# power.net
KiCad netlist of a schematic drawn in Altium Designer
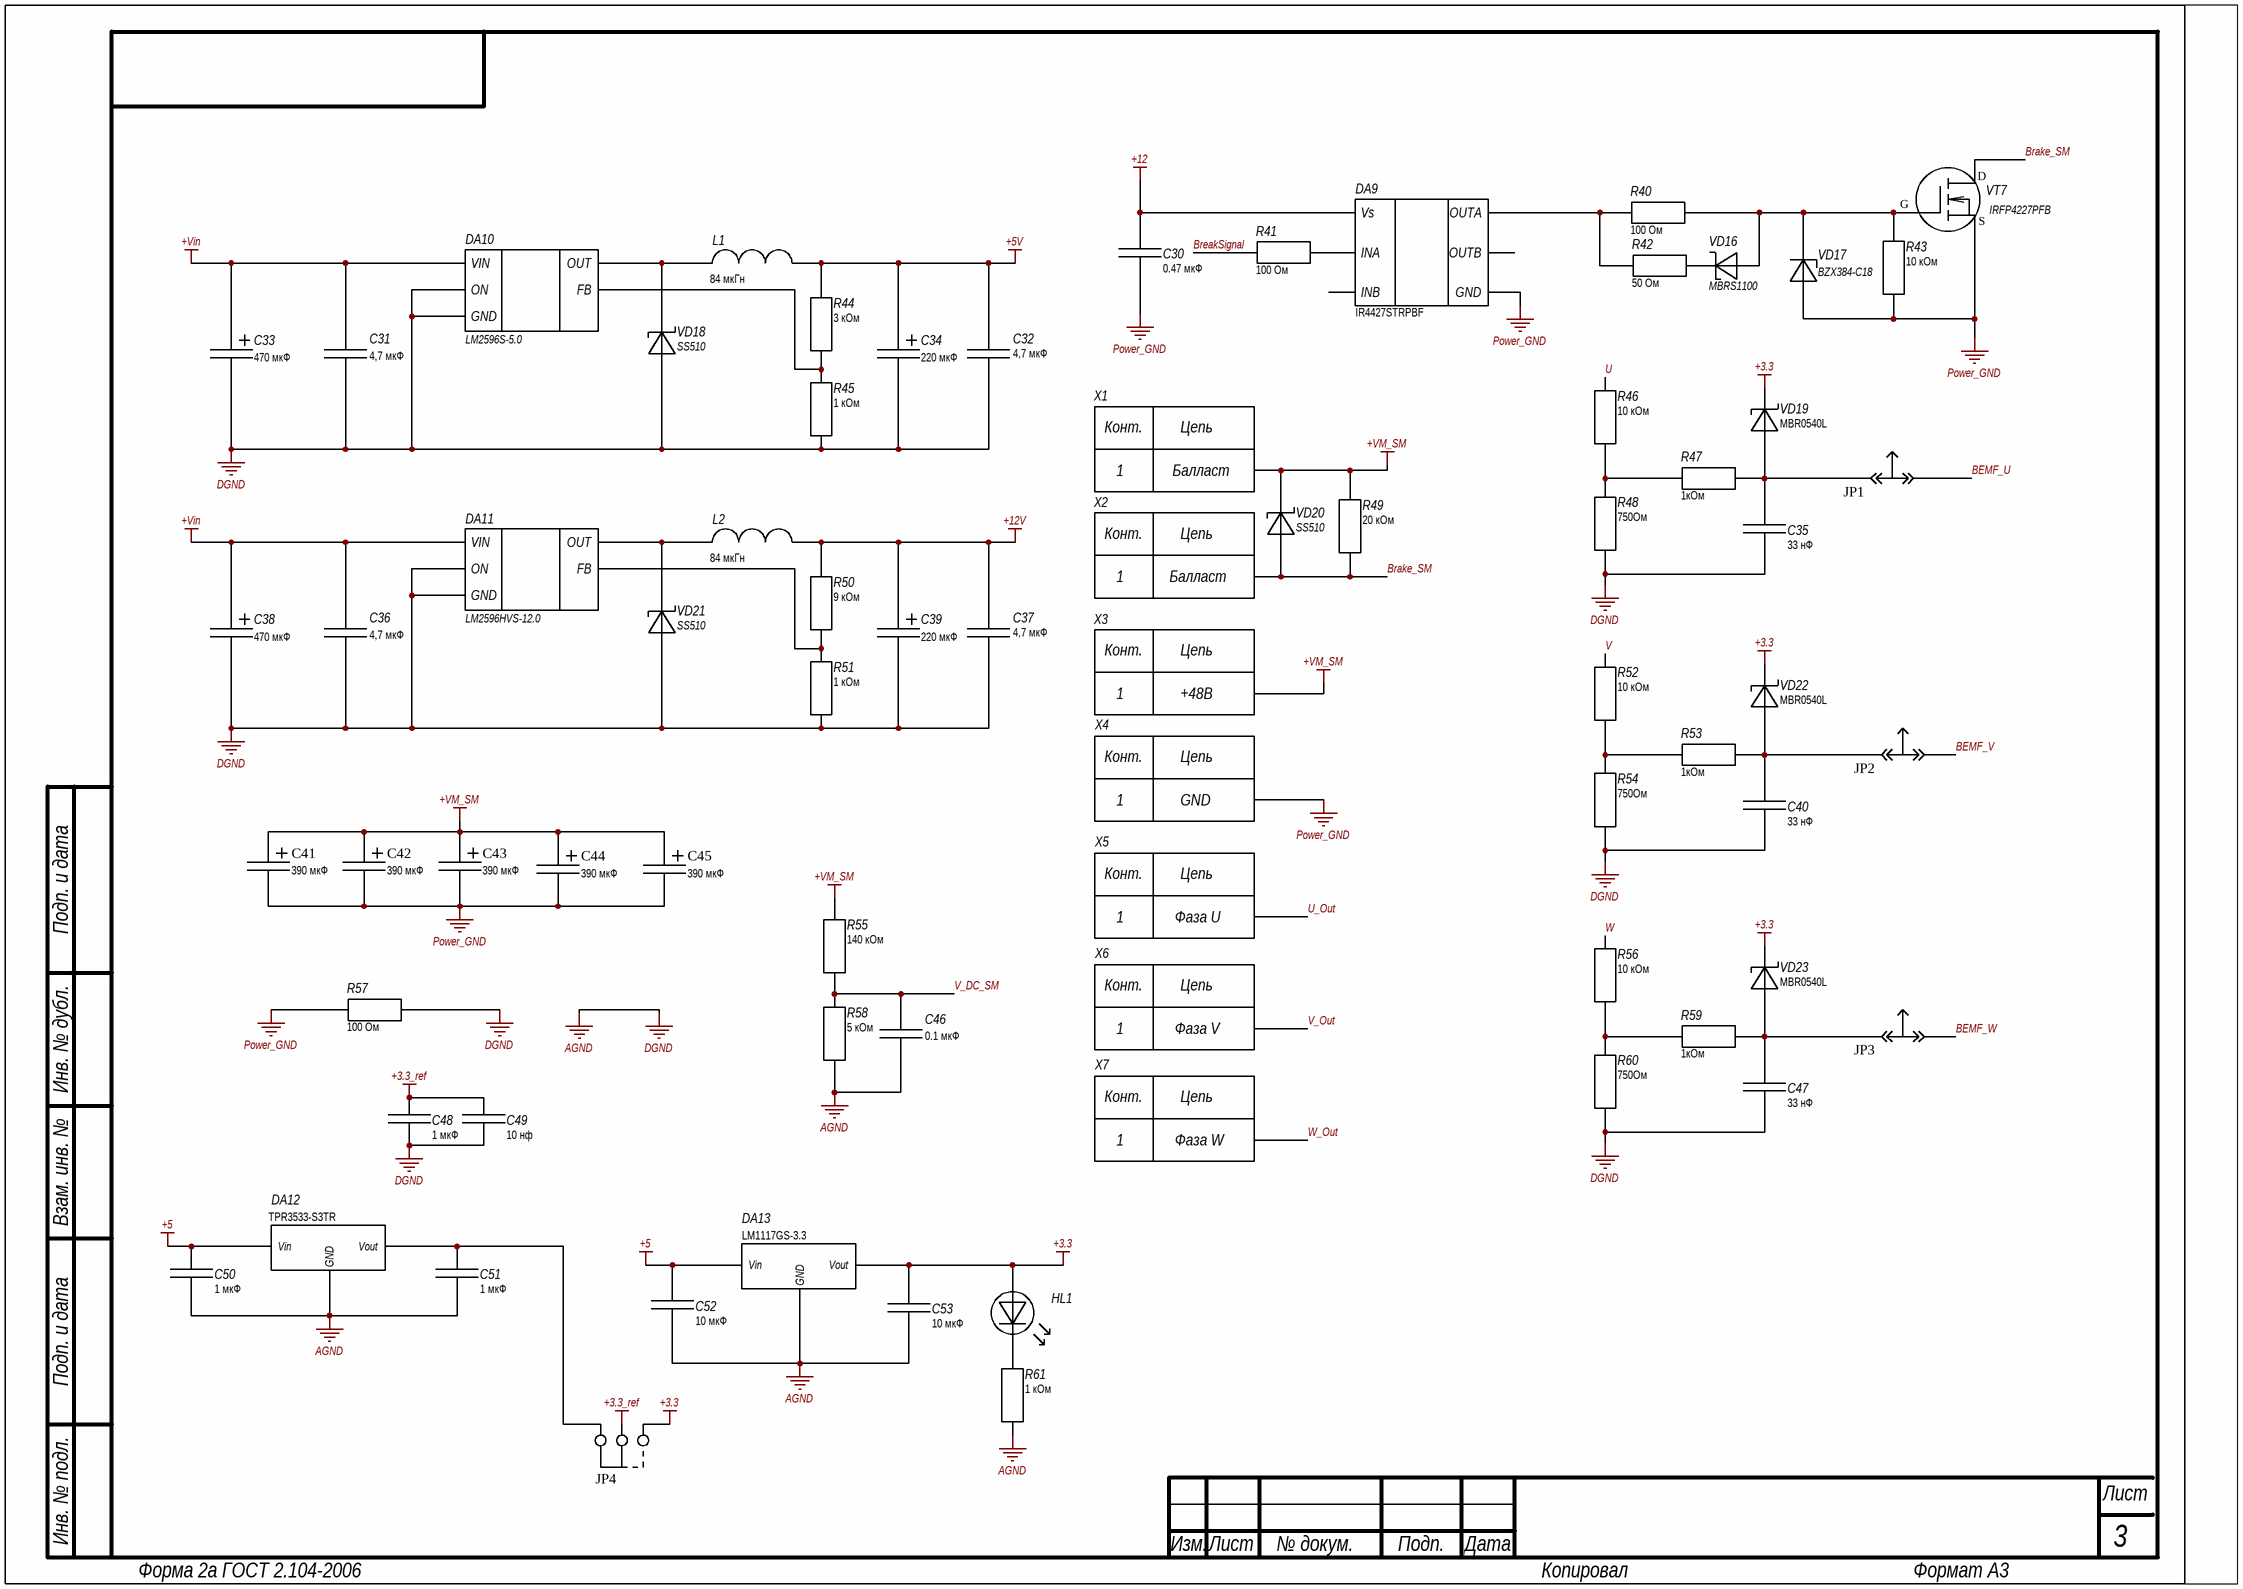
[diagram p0: power.SchDoc]

(export (version "E")
  (design (tool "Eeschema 10.0.6"))
  (components
    (comp (ref "1")
      (value "Net Tie")
      (footprint "Net Tie")
      (libsource (lib "Main_components") (part "Net Tie"))
    )
    (comp (ref "C30")
      (value "0.47 мкФ")
      (footprint "CC1206")
      (fields (field (name "VOLTAGE") "50В") (field (name "Comment") "Capacitor"))
      (libsource (lib "Main_components") (part "Capacitor"))
    )
    (comp (ref "C31")
      (value "4,7 мкФ")
      (footprint "CC1206")
      (fields (field (name "VOLTAGE") "50 В") (field (name "Comment") "Capacitor"))
      (libsource (lib "Main_components") (part "Capacitor"))
    )
    (comp (ref "C32")
      (value "4,7 мкФ")
      (footprint "CC1206")
      (fields (field (name "VOLTAGE") "50 В") (field (name "Comment") "Capacitor"))
      (libsource (lib "Main_components") (part "Capacitor"))
    )
    (comp (ref "C33")
      (value "470 мкФ")
      (footprint "CAP-5-12.5")
      (fields (field (name "VOLTAGE") " 50 В") (field (name "Comment") "EXR471M50B"))
      (libsource (lib "Main_components") (part "Сapacitor pol"))
    )
    (comp (ref "C34")
      (value "220 мкФ")
      (footprint "CAP-5-10")
      (fields (field (name "VOLTAGE") "35 В") (field (name "Comment") "B41858C7227M"))
      (libsource (lib "Main_components") (part "Сapacitor pol"))
    )
    (comp (ref "C35")
      (value "33 нФ")
      (footprint "CC0805")
      (fields (field (name "VOLTAGE") "50В") (field (name "Comment") "Capacitor"))
      (libsource (lib "Main_components") (part "Capacitor"))
    )
    (comp (ref "C36")
      (value "4,7 мкФ")
      (footprint "CC1206")
      (fields (field (name "VOLTAGE") "50 В") (field (name "Comment") "Capacitor"))
      (libsource (lib "Main_components") (part "Capacitor"))
    )
    (comp (ref "C37")
      (value "4,7 мкФ")
      (footprint "CC1206")
      (fields (field (name "VOLTAGE") "50 В") (field (name "Comment") "Capacitor"))
      (libsource (lib "Main_components") (part "Capacitor"))
    )
    (comp (ref "C38")
      (value "470 мкФ")
      (footprint "CAP-5-12.5")
      (fields (field (name "VOLTAGE") " 50 В") (field (name "Comment") "EXR471M50B"))
      (libsource (lib "Main_components") (part "Сapacitor pol"))
    )
    (comp (ref "C39")
      (value "220 мкФ")
      (footprint "CAP-5-10")
      (fields (field (name "VOLTAGE") "35 В") (field (name "Comment") "B41858C7227M"))
      (libsource (lib "Main_components") (part "Сapacitor pol"))
    )
    (comp (ref "C40")
      (value "33 нФ")
      (footprint "CC0805")
      (fields (field (name "VOLTAGE") "50В") (field (name "Comment") "Capacitor"))
      (libsource (lib "Main_components") (part "Capacitor"))
    )
    (comp (ref "C41")
      (value "390 мкФ")
      (footprint "CAP-7.5-18")
      (fields (field (name "Comment") "Сapacitor pol"))
      (libsource (lib "Main_components") (part "Сapacitor pol"))
    )
    (comp (ref "C42")
      (value "390 мкФ")
      (footprint "CAP-7.5-18")
      (fields (field (name "Comment") "Сapacitor pol"))
      (libsource (lib "Main_components") (part "Сapacitor pol"))
    )
    (comp (ref "C43")
      (value "390 мкФ")
      (footprint "CAP-7.5-18")
      (fields (field (name "Comment") "Сapacitor pol"))
      (libsource (lib "Main_components") (part "Сapacitor pol"))
    )
    (comp (ref "C44")
      (value "390 мкФ")
      (footprint "CAP-7.5-18")
      (fields (field (name "Comment") "Сapacitor pol"))
      (libsource (lib "Main_components") (part "Сapacitor pol"))
    )
    (comp (ref "C45")
      (value "390 мкФ")
      (footprint "CAP-7.5-18")
      (fields (field (name "Comment") "Сapacitor pol"))
      (libsource (lib "Main_components") (part "Сapacitor pol"))
    )
    (comp (ref "C46")
      (value "0.1 мкФ")
      (footprint "CC0603")
      (fields (field (name "VOLTAGE") "50 В") (field (name "Comment") "Capacitor"))
      (libsource (lib "Main_components") (part "Capacitor"))
    )
    (comp (ref "C47")
      (value "33 нФ")
      (footprint "CC0805")
      (fields (field (name "VOLTAGE") "50В") (field (name "Comment") "Capacitor"))
      (libsource (lib "Main_components") (part "Capacitor"))
    )
    (comp (ref "C48")
      (value "1 мкФ")
      (footprint "CC0603")
      (fields (field (name "VOLTAGE") "10В") (field (name "Comment") "Capacitor"))
      (libsource (lib "Main_components") (part "Capacitor"))
    )
    (comp (ref "C49")
      (value "10 нф")
      (footprint "CC0402")
      (fields (field (name "VOLTAGE") "16В") (field (name "Comment") "Capacitor"))
      (libsource (lib "Main_components") (part "Capacitor"))
    )
    (comp (ref "C50")
      (value "1 мкФ")
      (footprint "CC0805")
      (fields (field (name "VOLTAGE") " 25 В") (field (name "Comment") "Capacitor"))
      (libsource (lib "Main_components") (part "Capacitor"))
    )
    (comp (ref "C51")
      (value "1 мкФ")
      (footprint "CC0805")
      (fields (field (name "VOLTAGE") " 25 В") (field (name "Comment") "Capacitor"))
      (libsource (lib "Main_components") (part "Capacitor"))
    )
    (comp (ref "C52")
      (value "10 мкФ")
      (footprint "CC1206")
      (fields (field (name "VOLTAGE") " 25 В") (field (name "Comment") "Capacitor"))
      (libsource (lib "Main_components") (part "Capacitor"))
    )
    (comp (ref "C53")
      (value "10 мкФ")
      (footprint "CC1206")
      (fields (field (name "VOLTAGE") " 25 В") (field (name "Comment") "Capacitor"))
      (libsource (lib "Main_components") (part "Capacitor"))
    )
    (comp (ref "DA9")
      (value "IR4427STRPBF")
      (footprint "SO8")
      (description "Драйвер сдвоенный нижнего плеча 8SOIC")
      (libsource (lib "Microcircuits") (part "IR4427STRPBF"))
    )
    (comp (ref "DA10")
      (value "LM2596S-5.0")
      (footprint "TO263-5L")
      (libsource (lib "Microcircuits") (part "LM2596"))
    )
    (comp (ref "DA11")
      (value "LM2596HVS-12.0")
      (footprint "TO263-5L")
      (libsource (lib "Microcircuits") (part "LM2596"))
    )
    (comp (ref "DA12")
      (value "TPR3533-S3TR")
      (footprint "SOT-23-5")
      (description "Источник опорного напряжения 3.3В")
      (libsource (lib "Microcircuits") (part "TPR3533-S3TR"))
    )
    (comp (ref "DA13")
      (value "LM1117GS-3.3")
      (footprint "SOT-223")
      (description "Линейный регулятор с низким падением напряжения, +3.3 В, 1А")
      (libsource (lib "Microcircuits") (part "LM1117GS-3.3"))
    )
    (comp (ref "HL1") (value "LED") (footprint "CC1206") (libsource (lib "Main_components") (part "LED")))
    (comp (ref "JP1") (value "Jumper-2") (footprint "PLS2") (libsource (lib "Connectors") (part "Jumper-2")))
    (comp (ref "JP2") (value "Jumper-2") (footprint "PLS2") (libsource (lib "Connectors") (part "Jumper-2")))
    (comp (ref "JP3") (value "Jumper-2") (footprint "PLS2") (libsource (lib "Connectors") (part "Jumper-2")))
    (comp (ref "JP4") (value "Jumper") (footprint "PLS3") (libsource (lib "Connectors") (part "Jumper")))
    (comp (ref "L1")
      (value "84 мкГн")
      (footprint "CDRH127/LDNP-820MC")
      (fields (field (name "Comment") "CDRH127/LDNP-820MC"))
      (libsource (lib "Main_components") (part "Inductor"))
    )
    (comp (ref "L2")
      (value "84 мкГн")
      (footprint "CDRH127/LDNP-820MC")
      (fields (field (name "Comment") "CDRH127/LDNP-820MC"))
      (libsource (lib "Main_components") (part "Inductor"))
    )
    (comp (ref "R40")
      (value "100 Ом")
      (footprint "RC2512")
      (fields (field (name "POWER") "1 Вт") (field (name "Comment") "Resistor"))
      (libsource (lib "Main_components") (part "Resistor"))
    )
    (comp (ref "R41")
      (value "100 Ом")
      (footprint "RC0603")
      (fields (field (name "POWER") "100 мВт") (field (name "Comment") "Resistor"))
      (libsource (lib "Main_components") (part "Resistor"))
    )
    (comp (ref "R42")
      (value "50 Ом")
      (footprint "RC2512")
      (fields (field (name "POWER") "1 Вт") (field (name "Comment") "Resistor"))
      (libsource (lib "") (part "Resistor_1"))
    )
    (comp (ref "R43")
      (value "10 кОм")
      (footprint "RC0805")
      (fields (field (name "POWER") "125 мВт") (field (name "Comment") "Resistor"))
      (libsource (lib "Main_components") (part "Resistor"))
    )
    (comp (ref "R44")
      (value "3 кОм")
      (footprint "RC0805")
      (fields (field (name "POWER") "125 мВт") (field (name "Comment") "Resistor"))
      (libsource (lib "Main_components") (part "Resistor"))
    )
    (comp (ref "R45")
      (value "1 кОм")
      (footprint "RC0805")
      (fields (field (name "POWER") "125 мВт") (field (name "Comment") "Resistor"))
      (libsource (lib "Main_components") (part "Resistor"))
    )
    (comp (ref "R46")
      (value "10 кОм")
      (footprint "RC1206")
      (fields (field (name "POWER") "125 мВт") (field (name "Comment") "Resistor"))
      (libsource (lib "Main_components") (part "Resistor"))
    )
    (comp (ref "R47")
      (value "1кОм")
      (footprint "RC0805")
      (fields (field (name "POWER") "125 мВт") (field (name "Comment") "Resistor"))
      (libsource (lib "Main_components") (part "Resistor"))
    )
    (comp (ref "R48")
      (value "750Ом")
      (footprint "RC1206")
      (fields (field (name "POWER") "125 мВт") (field (name "Comment") "Resistor"))
      (libsource (lib "Main_components") (part "Resistor"))
    )
    (comp (ref "R49")
      (value "20 кОм")
      (footprint "RC1206")
      (fields (field (name "POWER") "250 мВт") (field (name "Comment") "Resistor"))
      (libsource (lib "Main_components") (part "Resistor"))
    )
    (comp (ref "R50")
      (value "9 кОм")
      (footprint "RC0805")
      (fields (field (name "POWER") "125 мВт") (field (name "Comment") "Resistor"))
      (libsource (lib "Main_components") (part "Resistor"))
    )
    (comp (ref "R51")
      (value "1 кОм")
      (footprint "RC0805")
      (fields (field (name "POWER") "125 мВт") (field (name "Comment") "Resistor"))
      (libsource (lib "Main_components") (part "Resistor"))
    )
    (comp (ref "R52")
      (value "10 кОм")
      (footprint "RC1206")
      (fields (field (name "POWER") "125 мВт") (field (name "Comment") "Resistor"))
      (libsource (lib "Main_components") (part "Resistor"))
    )
    (comp (ref "R53")
      (value "1кОм")
      (footprint "RC0805")
      (fields (field (name "POWER") "125 мВт") (field (name "Comment") "Resistor"))
      (libsource (lib "Main_components") (part "Resistor"))
    )
    (comp (ref "R54")
      (value "750Ом")
      (footprint "RC1206")
      (fields (field (name "POWER") "125 мВт") (field (name "Comment") "Resistor"))
      (libsource (lib "Main_components") (part "Resistor"))
    )
    (comp (ref "R55")
      (value "140 кОм")
      (footprint "RC1206")
      (fields (field (name "POWER") "250 мВт") (field (name "Comment") "Resistor"))
      (libsource (lib "Main_components") (part "Resistor"))
    )
    (comp (ref "R56")
      (value "10 кОм")
      (footprint "RC1206")
      (fields (field (name "POWER") "125 мВт") (field (name "Comment") "Resistor"))
      (libsource (lib "Main_components") (part "Resistor"))
    )
    (comp (ref "R57")
      (value "100 Ом")
      (footprint "RC2512")
      (fields (field (name "POWER") "1 Вт") (field (name "Comment") "Resistor"))
      (libsource (lib "Main_components") (part "Resistor"))
    )
    (comp (ref "R58")
      (value "5 кОм")
      (footprint "RC1206")
      (fields (field (name "POWER") "250 мВт") (field (name "Comment") "Resistor"))
      (libsource (lib "Main_components") (part "Resistor"))
    )
    (comp (ref "R59")
      (value "1кОм")
      (footprint "RC0805")
      (fields (field (name "POWER") "125 мВт") (field (name "Comment") "Resistor"))
      (libsource (lib "Main_components") (part "Resistor"))
    )
    (comp (ref "R60")
      (value "750Ом")
      (footprint "RC1206")
      (fields (field (name "POWER") "125 мВт") (field (name "Comment") "Resistor"))
      (libsource (lib "Main_components") (part "Resistor"))
    )
    (comp (ref "R61")
      (value "1 кОм")
      (footprint "RC0805")
      (fields (field (name "POWER") "125 мВт") (field (name "Comment") "Resistor"))
      (libsource (lib "Main_components") (part "Resistor"))
    )
    (comp (ref "VD16")
      (value "MBRS1100")
      (footprint "DO-214AA")
      (libsource (lib "Main_components") (part "Shotki"))
    )
    (comp (ref "VD17")
      (value "BZX384-C18")
      (footprint "SOD323")
      (libsource (lib "InvertorSchLib") (part "Zener diode"))
    )
    (comp (ref "VD18")
      (value "SS510")
      (footprint "DO214AB")
      (libsource (lib "Main_components") (part "Shotki"))
    )
    (comp (ref "VD19")
      (value "MBR0540L")
      (footprint "SOD123")
      (libsource (lib "Main_components") (part "Shotki"))
    )
    (comp (ref "VD20")
      (value "SS510")
      (footprint "DO214AB")
      (libsource (lib "Main_components") (part "Shotki"))
    )
    (comp (ref "VD21")
      (value "SS510")
      (footprint "DO214AB")
      (libsource (lib "Main_components") (part "Shotki"))
    )
    (comp (ref "VD22")
      (value "MBR0540L")
      (footprint "SOD123")
      (libsource (lib "Main_components") (part "Shotki"))
    )
    (comp (ref "VD23")
      (value "MBR0540L")
      (footprint "SOD123")
      (libsource (lib "Main_components") (part "Shotki"))
    )
    (comp (ref "VT7")
      (value "IRFP4227PFB")
      (footprint "TO247-1")
      (libsource (lib "InvertorSchLib") (part "N-MOSFET"))
    )
    (comp (ref "X1")
      (value "Connector-1")
      (footprint "PCBM4")
      (libsource (lib "InvertorSchLib") (part "Connector-1"))
    )
    (comp (ref "X2")
      (value "Connector-1")
      (footprint "PCBM4")
      (libsource (lib "InvertorSchLib") (part "Connector-1"))
    )
    (comp (ref "X3")
      (value "Connector-1")
      (footprint "PCBM4")
      (libsource (lib "InvertorSchLib") (part "Connector-1"))
    )
    (comp (ref "X4")
      (value "Connector-1")
      (footprint "PCBM4")
      (libsource (lib "InvertorSchLib") (part "Connector-1"))
    )
    (comp (ref "X5")
      (value "Connector-1")
      (footprint "PCBM4")
      (libsource (lib "InvertorSchLib") (part "Connector-1"))
    )
    (comp (ref "X6")
      (value "Connector-1")
      (footprint "PCBM4")
      (libsource (lib "InvertorSchLib") (part "Connector-1"))
    )
    (comp (ref "X7")
      (value "Connector-1")
      (footprint "PCBM4")
      (libsource (lib "InvertorSchLib") (part "Connector-1"))
    )
  )
  (nets
    (net (code "1") (name "+3.3") (class "Default")
      (node (ref "C53") (pin "1") (pinfunction "1_1") (pintype "passive"))
      (node (ref "DA13") (pin "2") (pinfunction "Vout_2") (pintype "passive"))
      (node (ref "HL1") (pin "A") (pinfunction "A_A") (pintype "passive"))
      (node (ref "JP4") (pin "1") (pinfunction "4_1") (pintype "passive"))
      (node (ref "VD19") (pin "C") (pinfunction "C_C") (pintype "passive"))
      (node (ref "VD22") (pin "C") (pinfunction "C_C") (pintype "passive"))
      (node (ref "VD23") (pin "C") (pinfunction "C_C") (pintype "passive"))
    )
    (net (code "2") (name "+3.3_ref") (class "Default")
      (node (ref "C48") (pin "1") (pinfunction "1_1") (pintype "passive"))
      (node (ref "C49") (pin "1") (pinfunction "1_1") (pintype "passive"))
      (node (ref "JP4") (pin "2") (pinfunction "5_2") (pintype "passive"))
    )
    (net (code "3") (name "+5") (class "Default")
      (node (ref "C50") (pin "1") (pinfunction "1_1") (pintype "passive"))
      (node (ref "C52") (pin "1") (pinfunction "1_1") (pintype "passive"))
      (node (ref "DA12") (pin "1") (pinfunction "Vin_1") (pintype "passive"))
      (node (ref "DA13") (pin "3") (pinfunction "Vin_3") (pintype "passive"))
    )
    (net (code "4") (name "+5V") (class "Default")
      (node (ref "C32") (pin "2") (pinfunction "2_2") (pintype "passive"))
      (node (ref "C34") (pin "1") (pinfunction "1_1") (pintype "passive"))
      (node (ref "L1") (pin "2") (pinfunction "2_2") (pintype "passive"))
      (node (ref "R44") (pin "1") (pinfunction "1_1") (pintype "passive"))
    )
    (net (code "5") (name "+12") (class "Default")
      (node (ref "C30") (pin "2") (pinfunction "2_2") (pintype "passive"))
      (node (ref "DA9") (pin "6") (pinfunction "Vs_6") (pintype "passive"))
    )
    (net (code "6") (name "+12V") (class "Default")
      (node (ref "C37") (pin "2") (pinfunction "2_2") (pintype "passive"))
      (node (ref "C39") (pin "1") (pinfunction "1_1") (pintype "passive"))
      (node (ref "L2") (pin "2") (pinfunction "2_2") (pintype "passive"))
      (node (ref "R50") (pin "1") (pinfunction "1_1") (pintype "passive"))
    )
    (net (code "7") (name "+VM_SM") (class "Default")
      (node (ref "C41") (pin "1") (pinfunction "1_1") (pintype "passive"))
      (node (ref "C42") (pin "1") (pinfunction "1_1") (pintype "passive"))
      (node (ref "C43") (pin "1") (pinfunction "1_1") (pintype "passive"))
      (node (ref "C44") (pin "1") (pinfunction "1_1") (pintype "passive"))
      (node (ref "C45") (pin "1") (pinfunction "1_1") (pintype "passive"))
      (node (ref "R49") (pin "1") (pinfunction "1_1") (pintype "passive"))
      (node (ref "R55") (pin "1") (pinfunction "1_1") (pintype "passive"))
      (node (ref "VD20") (pin "C") (pinfunction "C_C") (pintype "passive"))
      (node (ref "X1") (pin "1") (pinfunction "1_1") (pintype "passive"))
      (node (ref "X3") (pin "1") (pinfunction "1_1") (pintype "passive"))
    )
    (net (code "8") (name "+Vin") (class "Default")
      (node (ref "C31") (pin "2") (pinfunction "2_2") (pintype "passive"))
      (node (ref "C33") (pin "1") (pinfunction "1_1") (pintype "passive"))
      (node (ref "C36") (pin "2") (pinfunction "2_2") (pintype "passive"))
      (node (ref "C38") (pin "1") (pinfunction "1_1") (pintype "passive"))
      (node (ref "DA10") (pin "1") (pinfunction "VIN_1") (pintype "passive"))
      (node (ref "DA11") (pin "1") (pinfunction "VIN_1") (pintype "passive"))
    )
    (net (code "9") (name "/BEMF_U") (class "Default")
      (node (ref "JP1") (pin "2") (pinfunction "4_2") (pintype "passive"))
    )
    (net (code "10") (name "/BEMF_V") (class "Default")
      (node (ref "JP2") (pin "2") (pinfunction "4_2") (pintype "passive"))
    )
    (net (code "11") (name "/BEMF_W") (class "Default")
      (node (ref "JP3") (pin "2") (pinfunction "4_2") (pintype "passive"))
    )
    (net (code "12") (name "/Brake_SM") (class "Default")
      (node (ref "R49") (pin "2") (pinfunction "2_2") (pintype "passive"))
      (node (ref "VD20") (pin "A") (pinfunction "A_A") (pintype "passive"))
      (node (ref "VT7") (pin "D") (pinfunction "D_D") (pintype "passive"))
      (node (ref "X2") (pin "1") (pinfunction "1_1") (pintype "passive"))
    )
    (net (code "13") (name "/BreakSignal") (class "Default")
      (node (ref "R41") (pin "2") (pinfunction "2_2") (pintype "passive"))
    )
    (net (code "14") (name "/U") (class "Default")
      (node (ref "R46") (pin "1") (pinfunction "1_1") (pintype "passive"))
    )
    (net (code "15") (name "/U_Out") (class "Default")
      (node (ref "X5") (pin "1") (pinfunction "1_1") (pintype "passive"))
    )
    (net (code "16") (name "/V") (class "Default")
      (node (ref "R52") (pin "1") (pinfunction "1_1") (pintype "passive"))
    )
    (net (code "17") (name "/V_DC_SM") (class "Default")
      (node (ref "C46") (pin "2") (pinfunction "2_2") (pintype "passive"))
      (node (ref "R55") (pin "2") (pinfunction "2_2") (pintype "passive"))
      (node (ref "R58") (pin "1") (pinfunction "1_1") (pintype "passive"))
    )
    (net (code "18") (name "/V_Out") (class "Default")
      (node (ref "X6") (pin "1") (pinfunction "1_1") (pintype "passive"))
    )
    (net (code "19") (name "/W") (class "Default")
      (node (ref "R56") (pin "1") (pinfunction "1_1") (pintype "passive"))
    )
    (net (code "20") (name "/W_Out") (class "Default")
      (node (ref "X7") (pin "1") (pinfunction "1_1") (pintype "passive"))
    )
    (net (code "21") (name "AGND") (class "Default")
      (node (ref "1") (pin "1") (pinfunction "1_1") (pintype "passive"))
      (node (ref "C46") (pin "1") (pinfunction "1_1") (pintype "passive"))
      (node (ref "C50") (pin "2") (pinfunction "2_2") (pintype "passive"))
      (node (ref "C51") (pin "2") (pinfunction "2_2") (pintype "passive"))
      (node (ref "C52") (pin "2") (pinfunction "2_2") (pintype "passive"))
      (node (ref "C53") (pin "2") (pinfunction "2_2") (pintype "passive"))
      (node (ref "DA12") (pin "3") (pinfunction "GND_3") (pintype "passive"))
      (node (ref "DA13") (pin "1") (pinfunction "GND_1") (pintype "passive"))
      (node (ref "R58") (pin "2") (pinfunction "2_2") (pintype "passive"))
      (node (ref "R61") (pin "2") (pinfunction "2_2") (pintype "passive"))
    )
    (net (code "22") (name "DGND") (class "Default")
      (node (ref "1") (pin "2") (pinfunction "2_2") (pintype "passive"))
      (node (ref "C31") (pin "1") (pinfunction "1_1") (pintype "passive"))
      (node (ref "C32") (pin "1") (pinfunction "1_1") (pintype "passive"))
      (node (ref "C33") (pin "2") (pinfunction "2_2") (pintype "passive"))
      (node (ref "C34") (pin "2") (pinfunction "2_2") (pintype "passive"))
      (node (ref "C35") (pin "1") (pinfunction "1_1") (pintype "passive"))
      (node (ref "C36") (pin "1") (pinfunction "1_1") (pintype "passive"))
      (node (ref "C37") (pin "1") (pinfunction "1_1") (pintype "passive"))
      (node (ref "C38") (pin "2") (pinfunction "2_2") (pintype "passive"))
      (node (ref "C39") (pin "2") (pinfunction "2_2") (pintype "passive"))
      (node (ref "C40") (pin "1") (pinfunction "1_1") (pintype "passive"))
      (node (ref "C47") (pin "1") (pinfunction "1_1") (pintype "passive"))
      (node (ref "C48") (pin "2") (pinfunction "2_2") (pintype "passive"))
      (node (ref "C49") (pin "2") (pinfunction "2_2") (pintype "passive"))
      (node (ref "DA10") (pin "3") (pinfunction "GND_3") (pintype "passive"))
      (node (ref "DA10") (pin "5") (pinfunction "ON_5") (pintype "passive"))
      (node (ref "DA11") (pin "3") (pinfunction "GND_3") (pintype "passive"))
      (node (ref "DA11") (pin "5") (pinfunction "ON_5") (pintype "passive"))
      (node (ref "R45") (pin "2") (pinfunction "2_2") (pintype "passive"))
      (node (ref "R48") (pin "2") (pinfunction "2_2") (pintype "passive"))
      (node (ref "R51") (pin "2") (pinfunction "2_2") (pintype "passive"))
      (node (ref "R54") (pin "2") (pinfunction "2_2") (pintype "passive"))
      (node (ref "R57") (pin "1") (pinfunction "1_1") (pintype "passive"))
      (node (ref "R60") (pin "2") (pinfunction "2_2") (pintype "passive"))
      (node (ref "VD18") (pin "A") (pinfunction "A_A") (pintype "passive"))
      (node (ref "VD21") (pin "A") (pinfunction "A_A") (pintype "passive"))
    )
    (net (code "23") (name "Net-(C35-Pad2)") (class "Default")
      (node (ref "C35") (pin "2") (pinfunction "2_2") (pintype "passive"))
      (node (ref "JP1") (pin "1") (pinfunction "4_1") (pintype "passive"))
      (node (ref "R47") (pin "2") (pinfunction "2_2") (pintype "passive"))
      (node (ref "VD19") (pin "A") (pinfunction "A_A") (pintype "passive"))
    )
    (net (code "24") (name "Net-(C40-Pad2)") (class "Default")
      (node (ref "C40") (pin "2") (pinfunction "2_2") (pintype "passive"))
      (node (ref "JP2") (pin "1") (pinfunction "4_1") (pintype "passive"))
      (node (ref "R53") (pin "2") (pinfunction "2_2") (pintype "passive"))
      (node (ref "VD22") (pin "A") (pinfunction "A_A") (pintype "passive"))
    )
    (net (code "25") (name "Net-(C47-Pad2)") (class "Default")
      (node (ref "C47") (pin "2") (pinfunction "2_2") (pintype "passive"))
      (node (ref "JP3") (pin "1") (pinfunction "4_1") (pintype "passive"))
      (node (ref "R59") (pin "2") (pinfunction "2_2") (pintype "passive"))
      (node (ref "VD23") (pin "A") (pinfunction "A_A") (pintype "passive"))
    )
    (net (code "26") (name "Net-(DA9-INA)") (class "Default")
      (node (ref "DA9") (pin "2") (pinfunction "INA_2") (pintype "passive"))
      (node (ref "R41") (pin "1") (pinfunction "1_1") (pintype "passive"))
    )
    (net (code "27") (name "Net-(DA9-OUTA)") (class "Default")
      (node (ref "DA9") (pin "7") (pinfunction "OUTA_7") (pintype "passive"))
      (node (ref "R40") (pin "2") (pinfunction "2_2") (pintype "passive"))
      (node (ref "R42") (pin "2") (pinfunction "2_2") (pintype "passive"))
    )
    (net (code "28") (name "Net-(DA10-FB)") (class "Default")
      (node (ref "DA10") (pin "4") (pinfunction "FB_4") (pintype "passive"))
      (node (ref "R44") (pin "2") (pinfunction "2_2") (pintype "passive"))
      (node (ref "R45") (pin "1") (pinfunction "1_1") (pintype "passive"))
    )
    (net (code "29") (name "Net-(DA10-OUT)") (class "Default")
      (node (ref "DA10") (pin "2") (pinfunction "OUT_2") (pintype "passive"))
      (node (ref "L1") (pin "1") (pinfunction "1_1") (pintype "passive"))
      (node (ref "VD18") (pin "C") (pinfunction "C_C") (pintype "passive"))
    )
    (net (code "30") (name "Net-(DA11-FB)") (class "Default")
      (node (ref "DA11") (pin "4") (pinfunction "FB_4") (pintype "passive"))
      (node (ref "R50") (pin "2") (pinfunction "2_2") (pintype "passive"))
      (node (ref "R51") (pin "1") (pinfunction "1_1") (pintype "passive"))
    )
    (net (code "31") (name "Net-(DA11-OUT)") (class "Default")
      (node (ref "DA11") (pin "2") (pinfunction "OUT_2") (pintype "passive"))
      (node (ref "L2") (pin "1") (pinfunction "1_1") (pintype "passive"))
      (node (ref "VD21") (pin "C") (pinfunction "C_C") (pintype "passive"))
    )
    (net (code "32") (name "Net-(DA12-Vout)") (class "Default")
      (node (ref "C51") (pin "1") (pinfunction "1_1") (pintype "passive"))
      (node (ref "DA12") (pin "2") (pinfunction "Vout_2") (pintype "passive"))
      (node (ref "JP4") (pin "3") (pinfunction "6_3") (pintype "passive"))
    )
    (net (code "33") (name "Net-(HL1-PadC)") (class "Default")
      (node (ref "HL1") (pin "C") (pinfunction "C_C") (pintype "passive"))
      (node (ref "R61") (pin "1") (pinfunction "1_1") (pintype "passive"))
    )
    (net (code "34") (name "Net-(R40-Pad1)") (class "Default")
      (node (ref "R40") (pin "1") (pinfunction "1_1") (pintype "passive"))
      (node (ref "R43") (pin "1") (pinfunction "1_1") (pintype "passive"))
      (node (ref "VD16") (pin "A") (pinfunction "A_A") (pintype "passive"))
      (node (ref "VD17") (pin "C") (pinfunction "C_C") (pintype "passive"))
      (node (ref "VT7") (pin "G") (pinfunction "G_G") (pintype "passive"))
    )
    (net (code "35") (name "Net-(R42-Pad1)") (class "Default")
      (node (ref "R42") (pin "1") (pinfunction "1_1") (pintype "passive"))
      (node (ref "VD16") (pin "C") (pinfunction "C_C") (pintype "passive"))
    )
    (net (code "36") (name "Net-(R46-Pad2)") (class "Default")
      (node (ref "R46") (pin "2") (pinfunction "2_2") (pintype "passive"))
      (node (ref "R47") (pin "1") (pinfunction "1_1") (pintype "passive"))
      (node (ref "R48") (pin "1") (pinfunction "1_1") (pintype "passive"))
    )
    (net (code "37") (name "Net-(R52-Pad2)") (class "Default")
      (node (ref "R52") (pin "2") (pinfunction "2_2") (pintype "passive"))
      (node (ref "R53") (pin "1") (pinfunction "1_1") (pintype "passive"))
      (node (ref "R54") (pin "1") (pinfunction "1_1") (pintype "passive"))
    )
    (net (code "38") (name "Net-(R56-Pad2)") (class "Default")
      (node (ref "R56") (pin "2") (pinfunction "2_2") (pintype "passive"))
      (node (ref "R59") (pin "1") (pinfunction "1_1") (pintype "passive"))
      (node (ref "R60") (pin "1") (pinfunction "1_1") (pintype "passive"))
    )
    (net (code "39") (name "Power_GND") (class "Default")
      (node (ref "C30") (pin "1") (pinfunction "1_1") (pintype "passive"))
      (node (ref "C41") (pin "2") (pinfunction "2_2") (pintype "passive"))
      (node (ref "C42") (pin "2") (pinfunction "2_2") (pintype "passive"))
      (node (ref "C43") (pin "2") (pinfunction "2_2") (pintype "passive"))
      (node (ref "C44") (pin "2") (pinfunction "2_2") (pintype "passive"))
      (node (ref "C45") (pin "2") (pinfunction "2_2") (pintype "passive"))
      (node (ref "DA9") (pin "3") (pinfunction "GND_3") (pintype "passive"))
      (node (ref "R43") (pin "2") (pinfunction "2_2") (pintype "passive"))
      (node (ref "R57") (pin "2") (pinfunction "2_2") (pintype "passive"))
      (node (ref "VD17") (pin "A") (pinfunction "A_A") (pintype "passive"))
      (node (ref "VT7") (pin "S") (pinfunction "S_S") (pintype "passive"))
      (node (ref "X4") (pin "1") (pinfunction "1_1") (pintype "passive"))
    )
    (net (code "40") (name "unconnected-(DA9-INB-Pad4)") (class "Default")
      (node (ref "DA9") (pin "4") (pinfunction "INB_4") (pintype "passive"))
    )
    (net (code "41") (name "unconnected-(DA9-OUTB-Pad5)") (class "Default")
      (node (ref "DA9") (pin "5") (pinfunction "OUTB_5") (pintype "passive"))
    )
  )
)
